# Launch_Tower_Power_Interface_Board_v1-4.net
KiCad netlist of a schematic drawn in EAGLE
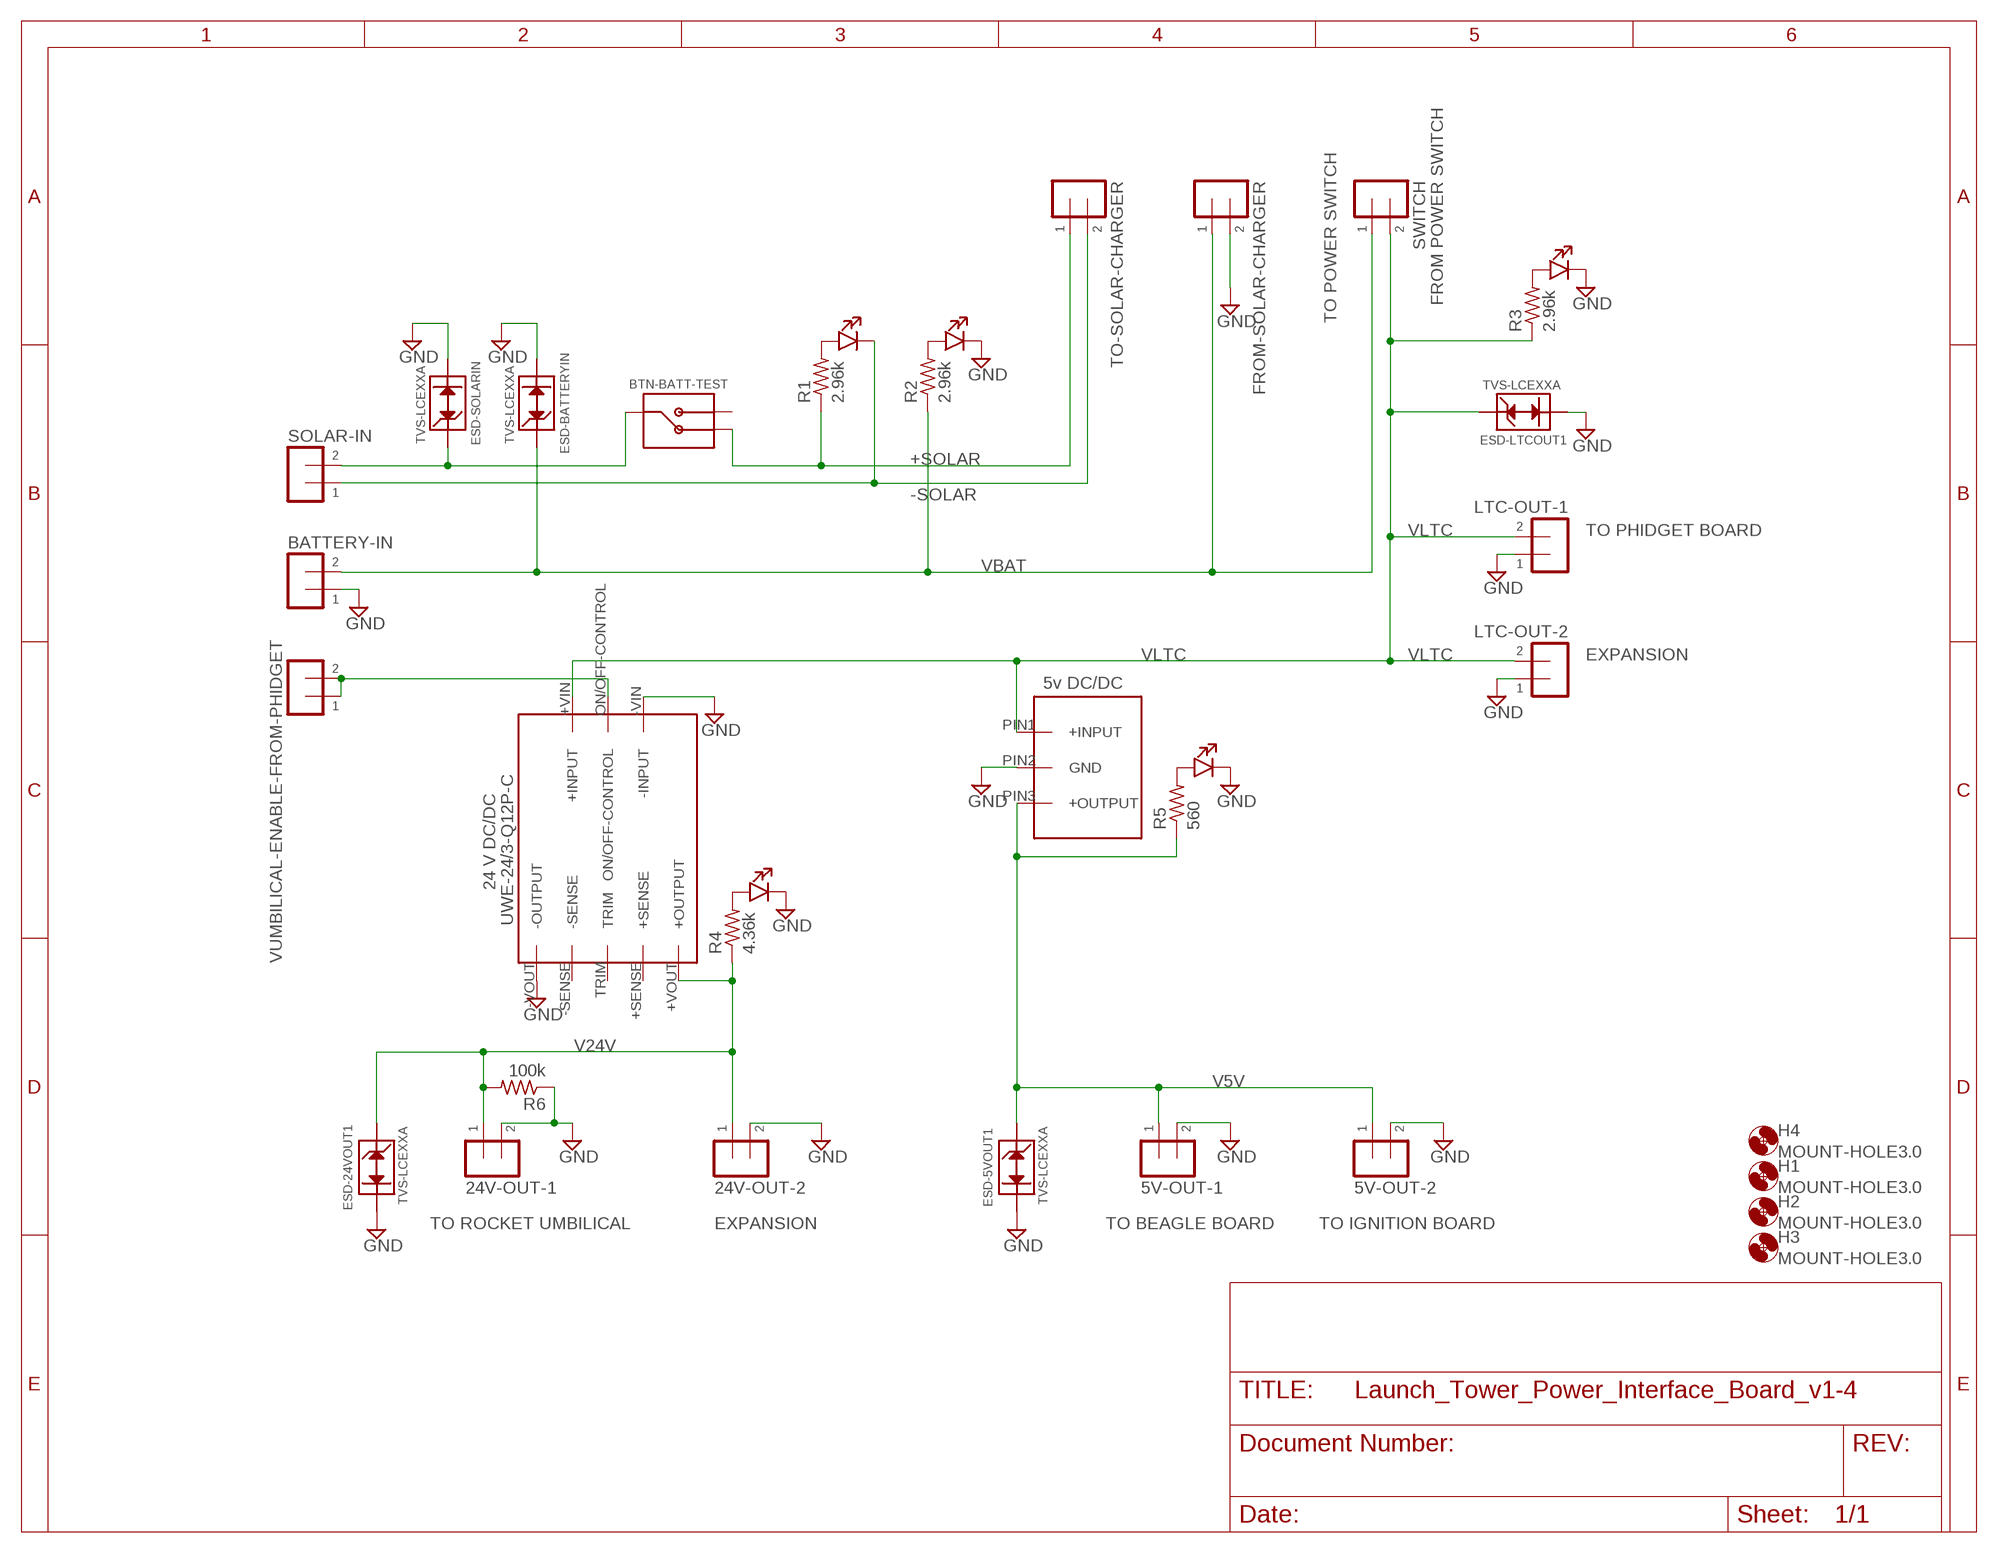
[diagram p0: schematic, sheet 1]

(export (version "E")
  (design (tool "Eeschema 10.0.6"))
  (components
    (comp (ref "5V-OUT-1")
      (value "SCREW-TERMINAL-5MM")
      (footprint "eagle-import:SCREW-TERM-5MM")
      (libsource (lib "eagle-import") (part "SCREW-TERMINAL-5MM"))
    )
    (comp (ref "5V-OUT-2")
      (value "SCREW-TERMINAL-5MM")
      (footprint "eagle-import:SCREW-TERM-5MM")
      (libsource (lib "eagle-import") (part "SCREW-TERMINAL-5MM"))
    )
    (comp (ref "24V-OUT-1")
      (value "SCREW-TERMINAL-5MM")
      (footprint "eagle-import:SCREW-TERM-5MM")
      (libsource (lib "eagle-import") (part "SCREW-TERMINAL-5MM"))
    )
    (comp (ref "24V-OUT-2")
      (value "SCREW-TERMINAL-5MM")
      (footprint "eagle-import:SCREW-TERM-5MM")
      (libsource (lib "eagle-import") (part "SCREW-TERMINAL-5MM"))
    )
    (comp (ref "BATTERY-IN")
      (value "SCREW-TERMINAL-5MM")
      (footprint "eagle-import:SCREW-TERM-5MM")
      (libsource (lib "eagle-import") (part "SCREW-TERMINAL-5MM"))
    )
    (comp (ref "BTN-BATT-TEST")
      (value "BUTTON-107-3006-EVX")
      (footprint "eagle-import:BUTTON-1")
      (libsource (lib "eagle-import") (part "BUTTON-107-3006-EVX"))
    )
    (comp (ref "DC1")
      (value "DC/DC_CONV_5V")
      (footprint "eagle-import:OKI-SIP")
      (libsource (lib "eagle-import") (part "DC/DC_CONV_5V"))
    )
    (comp (ref "DC2")
      (value "UWE-24/3-Q12P-C")
      (footprint "eagle-import:UWE")
      (libsource (lib "eagle-import") (part "DC/DC_CONV_24V"))
    )
    (comp (ref "ESD-5VOUT1")
      (value "TVS-LCEXXA")
      (footprint "eagle-import:D0-201")
      (libsource (lib "eagle-import") (part "TVS-LCEXXA"))
    )
    (comp (ref "ESD-24VOUT1")
      (value "TVS-LCEXXA")
      (footprint "eagle-import:D0-201")
      (libsource (lib "eagle-import") (part "TVS-LCEXXA"))
    )
    (comp (ref "ESD-BATTERYIN")
      (value "TVS-LCEXXA")
      (footprint "eagle-import:D0-201")
      (libsource (lib "eagle-import") (part "TVS-LCEXXA"))
    )
    (comp (ref "ESD-LTCOUT1")
      (value "TVS-LCEXXA")
      (footprint "eagle-import:D0-201")
      (libsource (lib "eagle-import") (part "TVS-LCEXXA"))
    )
    (comp (ref "ESD-SOLARIN")
      (value "TVS-LCEXXA")
      (footprint "eagle-import:D0-201")
      (libsource (lib "eagle-import") (part "TVS-LCEXXA"))
    )
    (comp (ref "FROM-SOLAR-CHARGER")
      (value "SCREW-TERMINAL-5MM")
      (footprint "eagle-import:SCREW-TERM-5MM")
      (libsource (lib "eagle-import") (part "SCREW-TERMINAL-5MM"))
    )
    (comp (ref "H1")
      (value "MOUNT-HOLE3.0")
      (footprint "eagle-import:3,0")
      (libsource (lib "eagle-import") (part "MOUNT-HOLE3.0"))
    )
    (comp (ref "H2")
      (value "MOUNT-HOLE3.0")
      (footprint "eagle-import:3,0")
      (libsource (lib "eagle-import") (part "MOUNT-HOLE3.0"))
    )
    (comp (ref "H3")
      (value "MOUNT-HOLE3.0")
      (footprint "eagle-import:3,0")
      (libsource (lib "eagle-import") (part "MOUNT-HOLE3.0"))
    )
    (comp (ref "H4")
      (value "MOUNT-HOLE3.0")
      (footprint "eagle-import:3,0")
      (libsource (lib "eagle-import") (part "MOUNT-HOLE3.0"))
    )
    (comp (ref "LED-5V-DC/DC")
      (value "LED-550-XX04")
      (footprint "eagle-import:LED-550")
      (libsource (lib "eagle-import") (part "LED-550-XX04"))
    )
    (comp (ref "LED-24V-DC/DC")
      (value "LED-550-XX04")
      (footprint "eagle-import:LED-550")
      (libsource (lib "eagle-import") (part "LED-550-XX04"))
    )
    (comp (ref "LED-BATTERY-IN")
      (value "LED-550-XX04")
      (footprint "eagle-import:LED-550")
      (libsource (lib "eagle-import") (part "LED-550-XX04"))
    )
    (comp (ref "LED-SOLAR-IN")
      (value "LED-550-XX04")
      (footprint "eagle-import:LED-550")
      (libsource (lib "eagle-import") (part "LED-550-XX04"))
    )
    (comp (ref "LED-SWITCH-IN")
      (value "LED-550-XX04")
      (footprint "eagle-import:LED-550")
      (libsource (lib "eagle-import") (part "LED-550-XX04"))
    )
    (comp (ref "LTC-OUT-1")
      (value "SCREW-TERMINAL-5MM")
      (footprint "eagle-import:SCREW-TERM-5MM")
      (libsource (lib "eagle-import") (part "SCREW-TERMINAL-5MM"))
    )
    (comp (ref "LTC-OUT-2")
      (value "SCREW-TERMINAL-5MM")
      (footprint "eagle-import:SCREW-TERM-5MM")
      (libsource (lib "eagle-import") (part "SCREW-TERMINAL-5MM"))
    )
    (comp (ref "R1")
      (value "2.96k")
      (footprint "eagle-import:0805-B")
      (libsource (lib "eagle-import") (part "R-US_0805-B"))
    )
    (comp (ref "R2")
      (value "2.96k")
      (footprint "eagle-import:0805-B")
      (libsource (lib "eagle-import") (part "R-US_0805-B"))
    )
    (comp (ref "R3")
      (value "2.96k")
      (footprint "eagle-import:0805-B")
      (libsource (lib "eagle-import") (part "R-US_0805-B"))
    )
    (comp (ref "R4")
      (value "4.36k")
      (footprint "eagle-import:0805-B")
      (libsource (lib "eagle-import") (part "R-US_0805-B"))
    )
    (comp (ref "R5")
      (value "560")
      (footprint "eagle-import:0805-B")
      (libsource (lib "eagle-import") (part "R-US_0805-B"))
    )
    (comp (ref "R6")
      (value "100k")
      (footprint "eagle-import:0805-B")
      (libsource (lib "eagle-import") (part "R-US_0805-B"))
    )
    (comp (ref "SOLAR-IN")
      (value "SCREW-TERMINAL-5MM")
      (footprint "eagle-import:SCREW-TERM-5MM")
      (libsource (lib "eagle-import") (part "SCREW-TERMINAL-5MM"))
    )
    (comp (ref "SWITCH")
      (value "SCREW-TERMINAL-5MM")
      (footprint "eagle-import:SCREW-TERM-5MM")
      (libsource (lib "eagle-import") (part "SCREW-TERMINAL-5MM"))
    )
    (comp (ref "TO-SOLAR-CHARGER")
      (value "SCREW-TERMINAL-5MM")
      (footprint "eagle-import:SCREW-TERM-5MM")
      (libsource (lib "eagle-import") (part "SCREW-TERMINAL-5MM"))
    )
    (comp (ref "VUMBILICAL-ENABLE-FROM-PHIDGET")
      (value "SCREW-TERMINAL-5MM")
      (footprint "eagle-import:SCREW-TERM-5MM")
      (libsource (lib "eagle-import") (part "SCREW-TERMINAL-5MM"))
    )
  )
  (nets
    (net (code "1") (name "/+SOLAR") (class "Default")
      (node (ref "BTN-BATT-TEST") (pin "NC") (pinfunction "NC_NC") (pintype "bidirectional"))
      (node (ref "R1") (pin "1") (pinfunction "1_1") (pintype "passive"))
      (node (ref "TO-SOLAR-CHARGER") (pin "1") (pinfunction "1_1") (pintype "passive"))
    )
    (net (code "2") (name "/-SOLAR") (class "Default")
      (node (ref "LED-SOLAR-IN") (pin "CATHODE") (pinfunction "CATHODE_CATHODE") (pintype "bidirectional"))
      (node (ref "SOLAR-IN") (pin "1") (pinfunction "1_1") (pintype "passive"))
      (node (ref "TO-SOLAR-CHARGER") (pin "2") (pinfunction "2_2") (pintype "passive"))
    )
    (net (code "3") (name "/V5V") (class "Default")
      (node (ref "5V-OUT-1") (pin "1") (pinfunction "1_1") (pintype "passive"))
      (node (ref "5V-OUT-2") (pin "1") (pinfunction "1_1") (pintype "passive"))
      (node (ref "DC1") (pin "PIN3") (pinfunction "+OUTPUT_PIN3") (pintype "bidirectional"))
      (node (ref "ESD-5VOUT1") (pin "ANODE") (pinfunction "ANODE_ANODE") (pintype "bidirectional"))
      (node (ref "R5") (pin "1") (pinfunction "1_1") (pintype "passive"))
    )
    (net (code "4") (name "/V24V") (class "Default")
      (node (ref "24V-OUT-1") (pin "1") (pinfunction "1_1") (pintype "passive"))
      (node (ref "24V-OUT-2") (pin "1") (pinfunction "1_1") (pintype "passive"))
      (node (ref "DC2") (pin "+VOUT") (pinfunction "+OUTPUT_+VOUT") (pintype "bidirectional"))
      (node (ref "ESD-24VOUT1") (pin "ANODE") (pinfunction "ANODE_ANODE") (pintype "bidirectional"))
      (node (ref "R4") (pin "1") (pinfunction "1_1") (pintype "passive"))
      (node (ref "R6") (pin "2") (pinfunction "2_2") (pintype "passive"))
    )
    (net (code "5") (name "/VBAT") (class "Default")
      (node (ref "BATTERY-IN") (pin "2") (pinfunction "2_2") (pintype "passive"))
      (node (ref "ESD-BATTERYIN") (pin "ANODE") (pinfunction "ANODE_ANODE") (pintype "bidirectional"))
      (node (ref "FROM-SOLAR-CHARGER") (pin "1") (pinfunction "1_1") (pintype "passive"))
      (node (ref "R2") (pin "1") (pinfunction "1_1") (pintype "passive"))
      (node (ref "SWITCH") (pin "1") (pinfunction "1_1") (pintype "passive"))
    )
    (net (code "6") (name "/VLTC") (class "Default")
      (node (ref "DC1") (pin "PIN1") (pinfunction "+INPUT_PIN1") (pintype "bidirectional"))
      (node (ref "DC2") (pin "+VIN") (pinfunction "+INPUT_+VIN") (pintype "bidirectional"))
      (node (ref "ESD-LTCOUT1") (pin "ANODE") (pinfunction "ANODE_ANODE") (pintype "bidirectional"))
      (node (ref "LTC-OUT-1") (pin "2") (pinfunction "2_2") (pintype "passive"))
      (node (ref "LTC-OUT-2") (pin "2") (pinfunction "2_2") (pintype "passive"))
      (node (ref "R3") (pin "1") (pinfunction "1_1") (pintype "passive"))
      (node (ref "SWITCH") (pin "2") (pinfunction "2_2") (pintype "passive"))
    )
    (net (code "7") (name "GND") (class "Default")
      (node (ref "24V-OUT-1") (pin "2") (pinfunction "2_2") (pintype "passive"))
      (node (ref "24V-OUT-2") (pin "2") (pinfunction "2_2") (pintype "passive"))
      (node (ref "5V-OUT-1") (pin "2") (pinfunction "2_2") (pintype "passive"))
      (node (ref "5V-OUT-2") (pin "2") (pinfunction "2_2") (pintype "passive"))
      (node (ref "BATTERY-IN") (pin "1") (pinfunction "1_1") (pintype "passive"))
      (node (ref "DC1") (pin "PIN2") (pinfunction "GND_PIN2") (pintype "bidirectional"))
      (node (ref "DC2") (pin "-VIN") (pinfunction "-INPUT_-VIN") (pintype "bidirectional"))
      (node (ref "DC2") (pin "-VOUT") (pinfunction "-OUTPUT_-VOUT") (pintype "bidirectional"))
      (node (ref "ESD-24VOUT1") (pin "CATHODE") (pinfunction "CATHODE_CATHODE") (pintype "bidirectional"))
      (node (ref "ESD-5VOUT1") (pin "CATHODE") (pinfunction "CATHODE_CATHODE") (pintype "bidirectional"))
      (node (ref "ESD-BATTERYIN") (pin "CATHODE") (pinfunction "CATHODE_CATHODE") (pintype "bidirectional"))
      (node (ref "ESD-LTCOUT1") (pin "CATHODE") (pinfunction "CATHODE_CATHODE") (pintype "bidirectional"))
      (node (ref "ESD-SOLARIN") (pin "CATHODE") (pinfunction "CATHODE_CATHODE") (pintype "bidirectional"))
      (node (ref "FROM-SOLAR-CHARGER") (pin "2") (pinfunction "2_2") (pintype "passive"))
      (node (ref "LED-24V-DC/DC") (pin "CATHODE") (pinfunction "CATHODE_CATHODE") (pintype "bidirectional"))
      (node (ref "LED-5V-DC/DC") (pin "CATHODE") (pinfunction "CATHODE_CATHODE") (pintype "bidirectional"))
      (node (ref "LED-BATTERY-IN") (pin "CATHODE") (pinfunction "CATHODE_CATHODE") (pintype "bidirectional"))
      (node (ref "LED-SWITCH-IN") (pin "CATHODE") (pinfunction "CATHODE_CATHODE") (pintype "bidirectional"))
      (node (ref "LTC-OUT-1") (pin "1") (pinfunction "1_1") (pintype "passive"))
      (node (ref "LTC-OUT-2") (pin "1") (pinfunction "1_1") (pintype "passive"))
      (node (ref "R6") (pin "1") (pinfunction "1_1") (pintype "passive"))
    )
    (net (code "8") (name "Net-(BTN-BATT-TEST-PadCOMMON)") (class "Default")
      (node (ref "BTN-BATT-TEST") (pin "COMMON") (pinfunction "COMMON_COMMON") (pintype "bidirectional"))
      (node (ref "ESD-SOLARIN") (pin "ANODE") (pinfunction "ANODE_ANODE") (pintype "bidirectional"))
      (node (ref "SOLAR-IN") (pin "2") (pinfunction "2_2") (pintype "passive"))
    )
    (net (code "9") (name "Net-(DC2-PadON{slash}OFF-CONTROL)") (class "Default")
      (node (ref "DC2") (pin "ON/OFF-CONTROL") (pinfunction "ON/OFF-CONTROL_ON/OFF-CONTROL") (pintype "bidirectional"))
      (node (ref "VUMBILICAL-ENABLE-FROM-PHIDGET") (pin "1") (pinfunction "1_1") (pintype "passive"))
      (node (ref "VUMBILICAL-ENABLE-FROM-PHIDGET") (pin "2") (pinfunction "2_2") (pintype "passive"))
    )
    (net (code "10") (name "Net-(LED-5V-DC/DC-PadANODE)") (class "Default")
      (node (ref "LED-5V-DC/DC") (pin "ANODE") (pinfunction "ANODE_ANODE") (pintype "bidirectional"))
      (node (ref "R5") (pin "2") (pinfunction "2_2") (pintype "passive"))
    )
    (net (code "11") (name "Net-(LED-24V-DC/DC-PadANODE)") (class "Default")
      (node (ref "LED-24V-DC/DC") (pin "ANODE") (pinfunction "ANODE_ANODE") (pintype "bidirectional"))
      (node (ref "R4") (pin "2") (pinfunction "2_2") (pintype "passive"))
    )
    (net (code "12") (name "Net-(LED-BATTERY-IN-PadANODE)") (class "Default")
      (node (ref "LED-BATTERY-IN") (pin "ANODE") (pinfunction "ANODE_ANODE") (pintype "bidirectional"))
      (node (ref "R2") (pin "2") (pinfunction "2_2") (pintype "passive"))
    )
    (net (code "13") (name "Net-(LED-SOLAR-IN-PadANODE)") (class "Default")
      (node (ref "LED-SOLAR-IN") (pin "ANODE") (pinfunction "ANODE_ANODE") (pintype "bidirectional"))
      (node (ref "R1") (pin "2") (pinfunction "2_2") (pintype "passive"))
    )
    (net (code "14") (name "Net-(LED-SWITCH-IN-PadANODE)") (class "Default")
      (node (ref "LED-SWITCH-IN") (pin "ANODE") (pinfunction "ANODE_ANODE") (pintype "bidirectional"))
      (node (ref "R3") (pin "2") (pinfunction "2_2") (pintype "passive"))
    )
    (net (code "15") (name "unconnected-(BTN-BATT-TEST-PadNO)") (class "Default")
      (node (ref "BTN-BATT-TEST") (pin "NO") (pinfunction "NO_NO") (pintype "bidirectional"))
    )
    (net (code "16") (name "unconnected-(DC2-Pad+SENSE)") (class "Default")
      (node (ref "DC2") (pin "+SENSE") (pinfunction "+SENSE_+SENSE") (pintype "bidirectional"))
    )
    (net (code "17") (name "unconnected-(DC2-Pad-SENSE)") (class "Default")
      (node (ref "DC2") (pin "-SENSE") (pinfunction "-SENSE_-SENSE") (pintype "bidirectional"))
    )
    (net (code "18") (name "unconnected-(DC2-PadTRIM)") (class "Default")
      (node (ref "DC2") (pin "TRIM") (pinfunction "TRIM_TRIM") (pintype "bidirectional"))
    )
  )
)
